# Telex-O.net
KiCad netlist of a schematic drawn in EAGLE
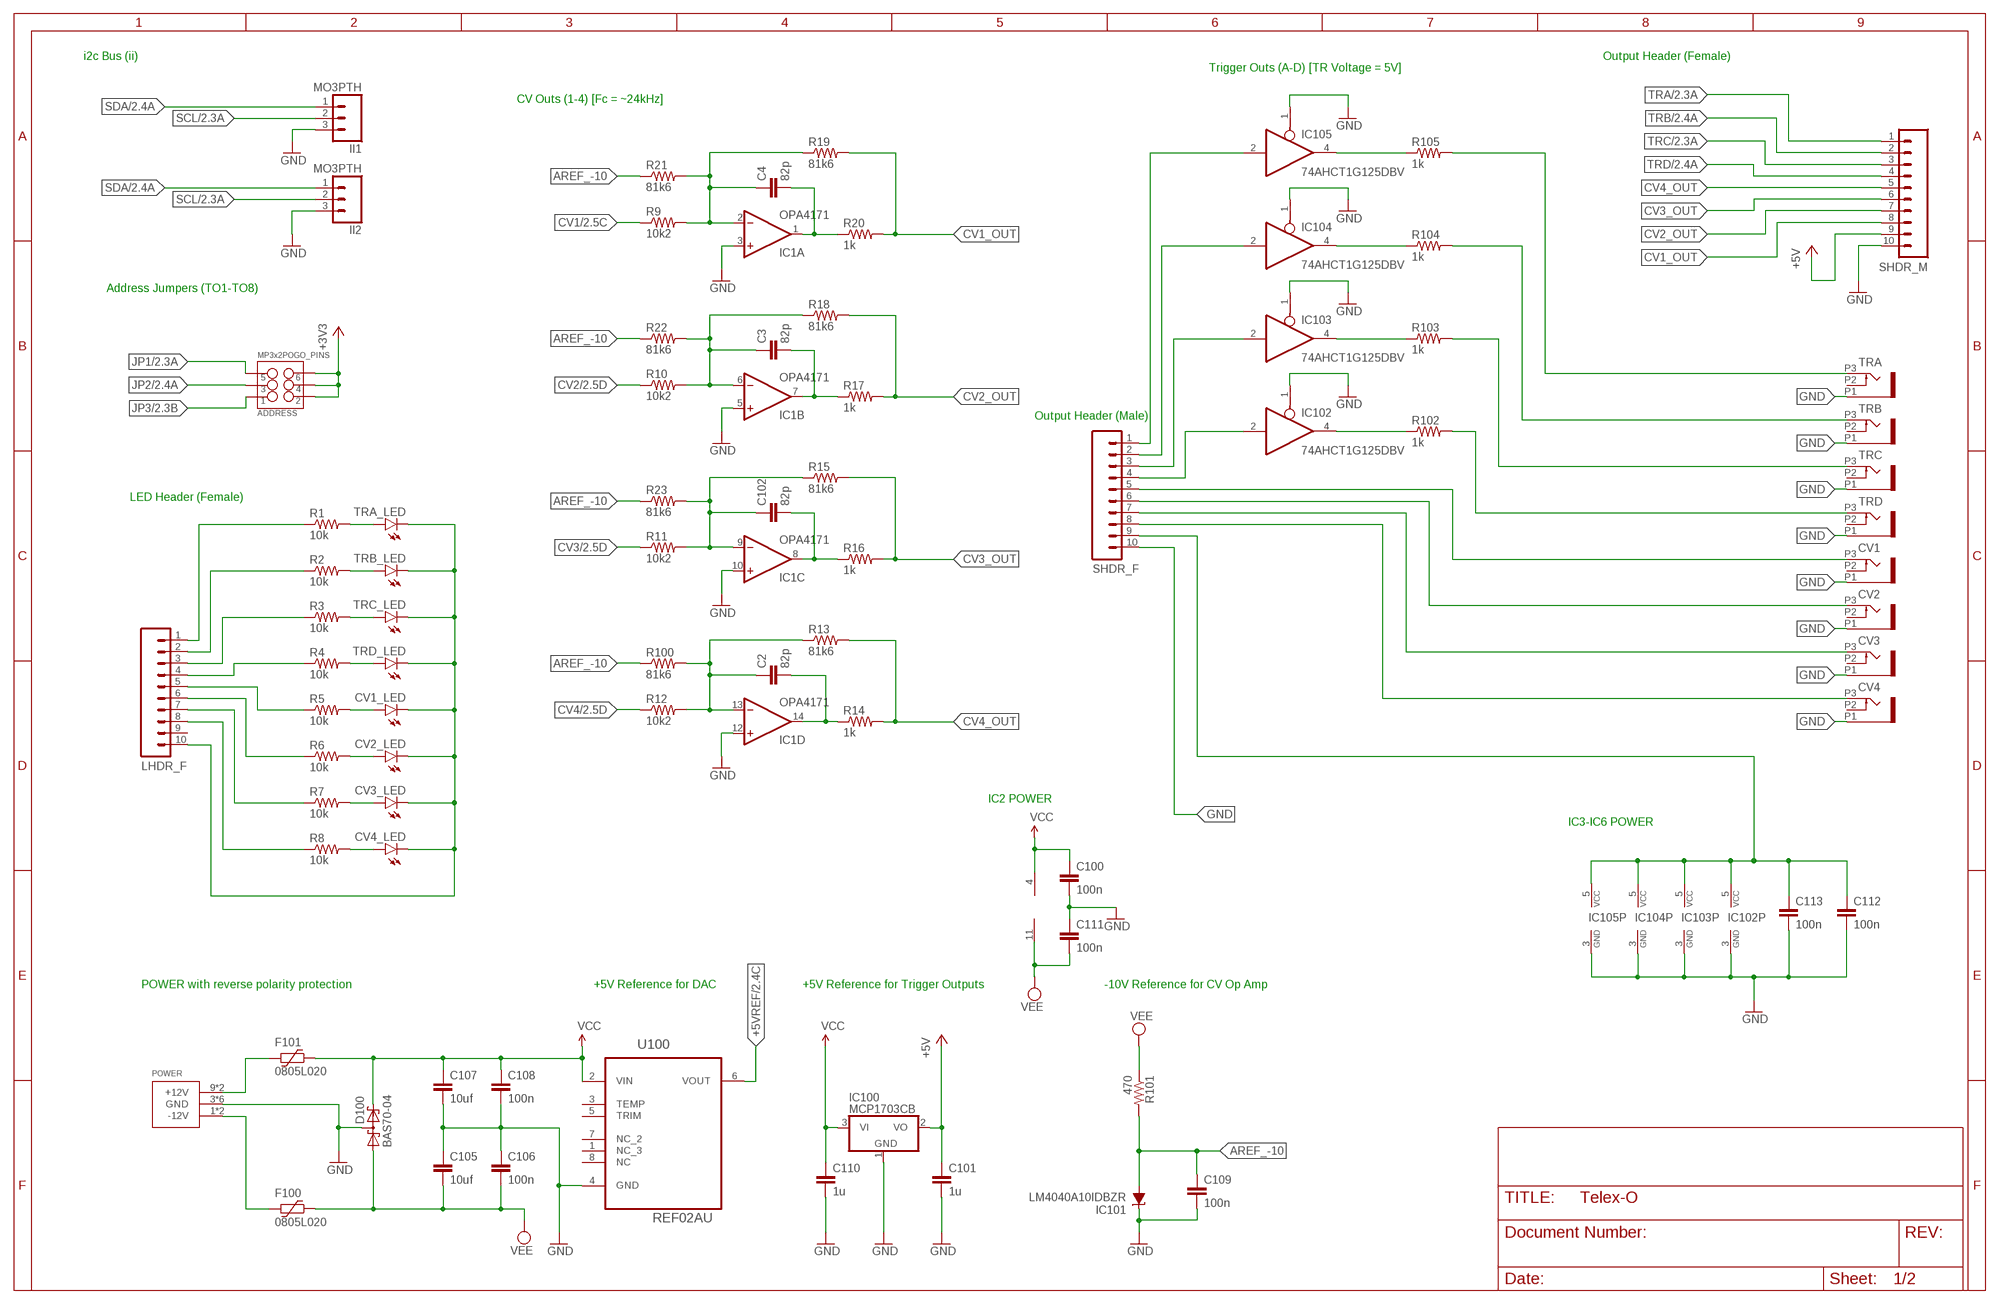
[diagram p0: schematic, sheet 1]
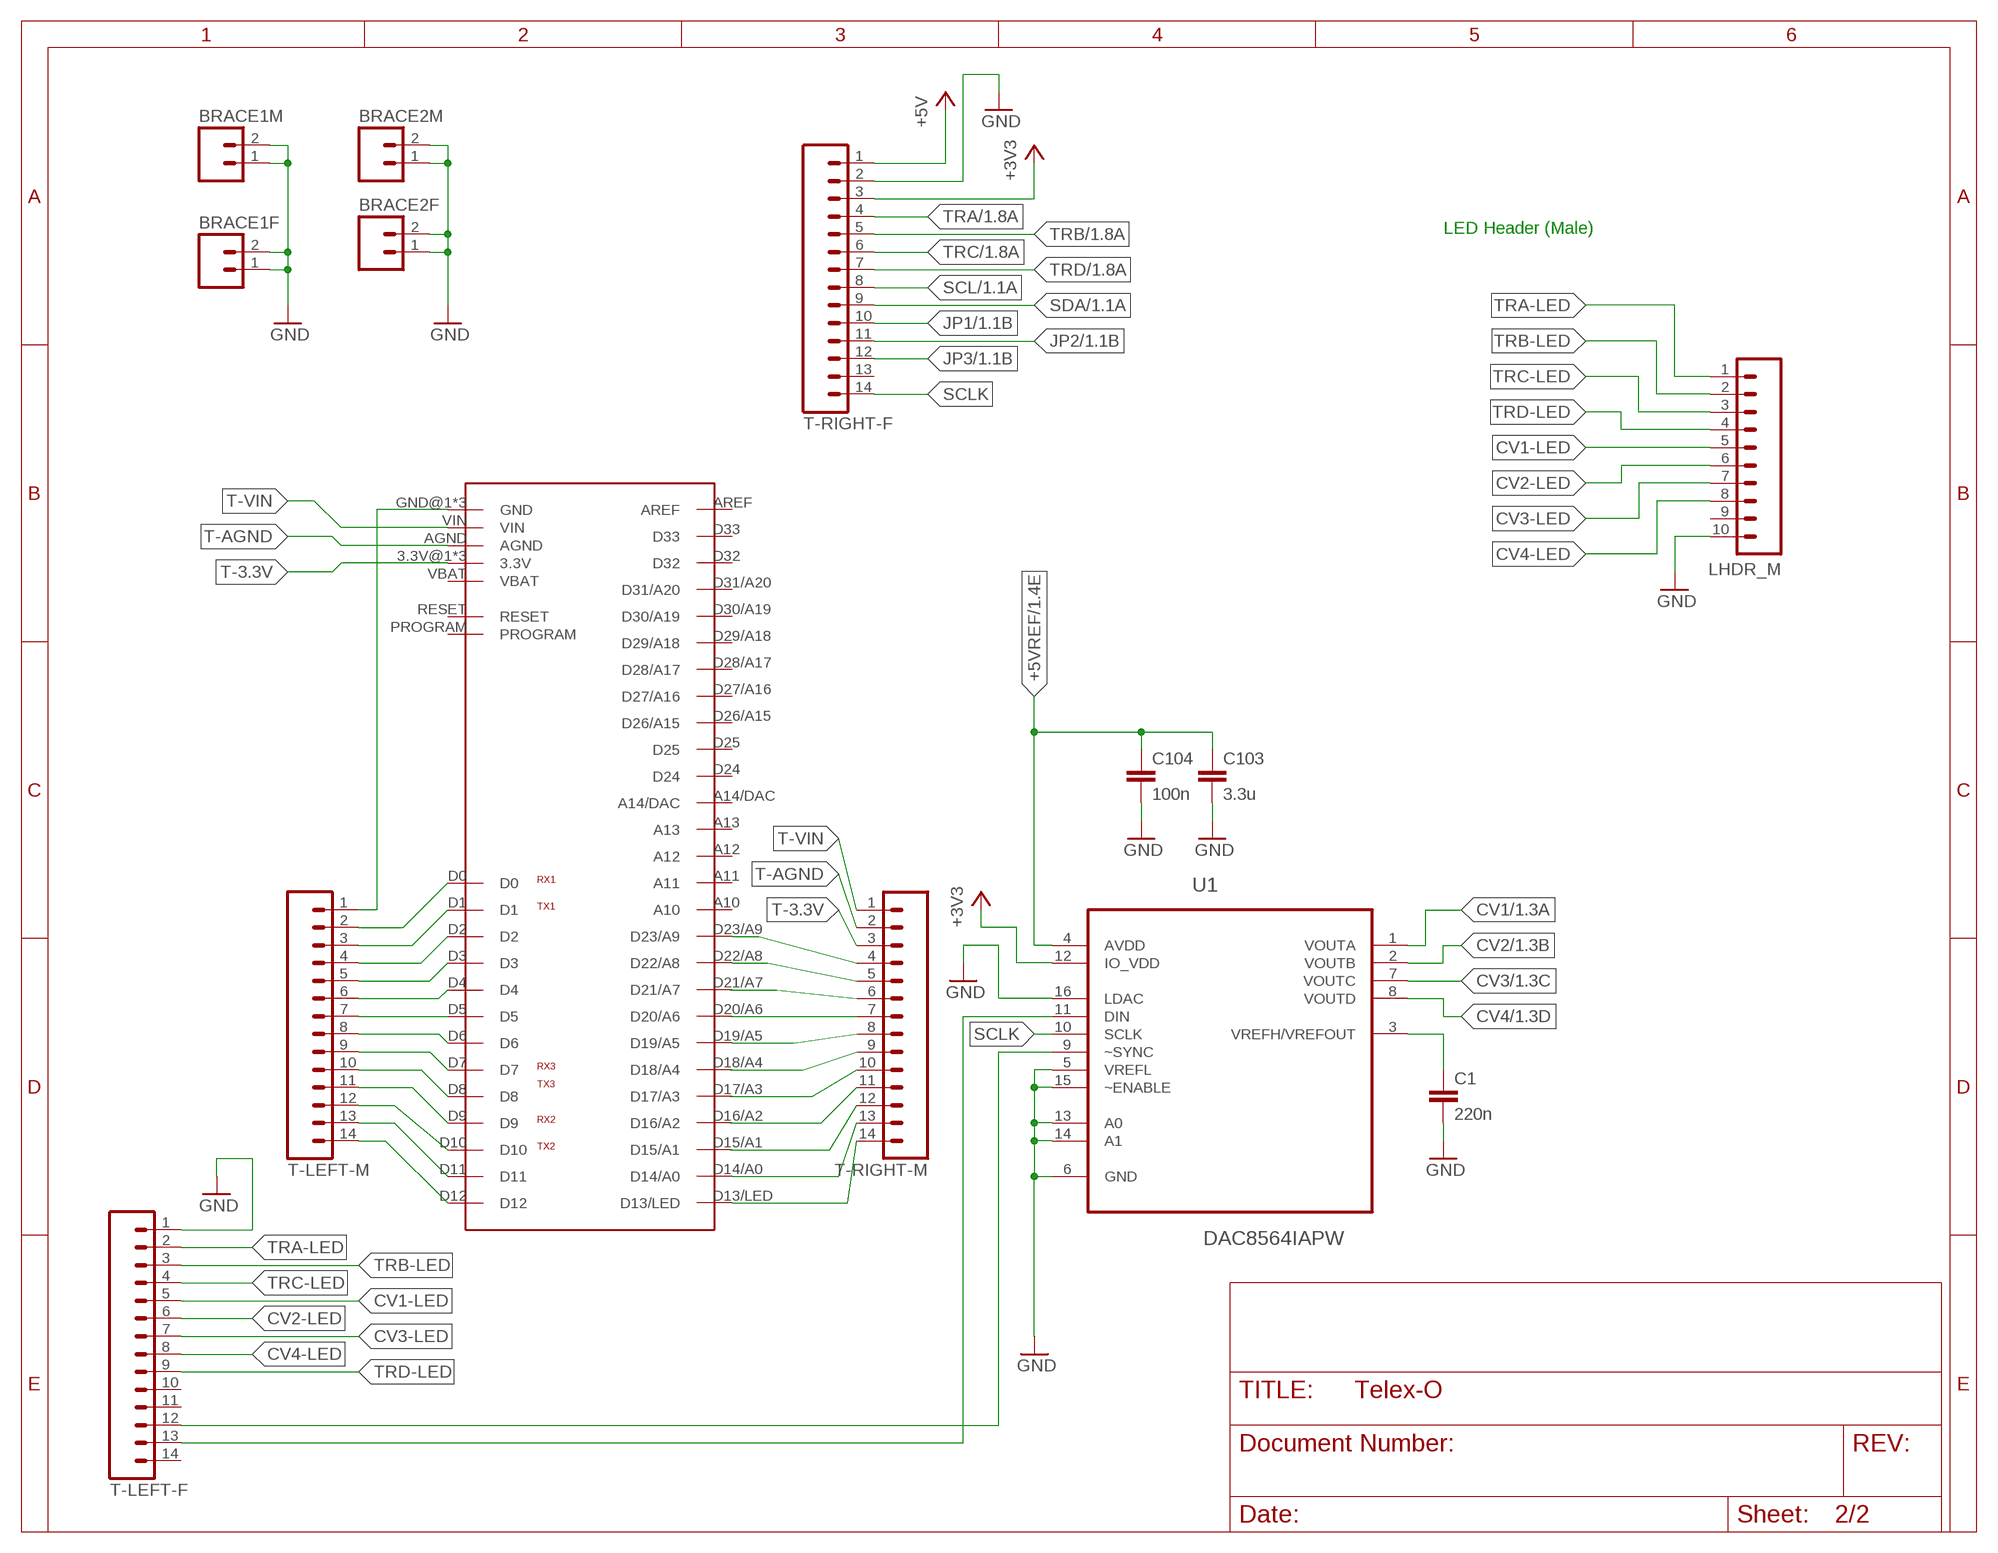
[diagram p1: schematic, sheet 2]

(export (version "E")
  (design (tool "Eeschema 10.0.6"))
  (components
    (comp (ref "BRACE1F")
      (value "M02PTH")
      (footprint "eagle-import:1X02")
      (libsource (lib "eagle-import") (part "M02PTH"))
    )
    (comp (ref "BRACE1M")
      (value "M02PTH")
      (footprint "eagle-import:1X02")
      (libsource (lib "eagle-import") (part "M02PTH"))
    )
    (comp (ref "BRACE2F")
      (value "M02PTH")
      (footprint "eagle-import:1X02")
      (libsource (lib "eagle-import") (part "M02PTH"))
    )
    (comp (ref "BRACE2M")
      (value "M02PTH")
      (footprint "eagle-import:1X02")
      (libsource (lib "eagle-import") (part "M02PTH"))
    )
    (comp (ref "C1")
      (value "220n")
      (footprint "eagle-import:0603-CAP")
      (libsource (lib "eagle-import") (part "CAP0603-CAP"))
    )
    (comp (ref "C103")
      (value "3.3u")
      (footprint "eagle-import:1206")
      (libsource (lib "eagle-import") (part "CAP1206"))
    )
    (comp (ref "C104")
      (value "100n")
      (footprint "eagle-import:0603-CAP")
      (libsource (lib "eagle-import") (part "CAP0603-CAP"))
    )
    (comp (ref "LHDR_M")
      (value "M10SILK_FEMALE_PTH")
      (footprint "eagle-import:1X10")
      (libsource (lib "eagle-import") (part "M10SILK_FEMALE_PTH"))
    )
    (comp (ref "T-LEFT-F")
      (value "M14")
      (footprint "eagle-import:1X14")
      (libsource (lib "eagle-import") (part "M14"))
    )
    (comp (ref "T-LEFT-M")
      (value "M14")
      (footprint "eagle-import:1X14")
      (libsource (lib "eagle-import") (part "M14"))
    )
    (comp (ref "T-RIGHT-F")
      (value "M14")
      (footprint "eagle-import:1X14")
      (libsource (lib "eagle-import") (part "M14"))
    )
    (comp (ref "T-RIGHT-M")
      (value "M14")
      (footprint "eagle-import:1X14")
      (libsource (lib "eagle-import") (part "M14"))
    )
    (comp (ref "U$1")
      (value "TEENSY3.1_ALL")
      (footprint "eagle-import:TEENSY3.1_ALL")
      (libsource (lib "eagle-import") (part "TEENSY3.1_ALL"))
    )
    (comp (ref "U1")
      (value "DAC8564IAPW")
      (footprint "eagle-import:SOP65P640X120-16N")
      (libsource (lib "eagle-import") (part "DAC8564IAPW"))
    )
    (comp (ref "ADDRESS")
      (value "MP3x2POGO_PINS")
      (footprint "eagle-import:2X3_POGO")
      (libsource (lib "eagle-import") (part "M03X2POGO_PINS"))
    )
    (comp (ref "C2")
      (value "82p")
      (footprint "eagle-import:1206")
      (libsource (lib "eagle-import") (part "CAP1206"))
    )
    (comp (ref "C3")
      (value "82p")
      (footprint "eagle-import:1206")
      (libsource (lib "eagle-import") (part "CAP1206"))
    )
    (comp (ref "C4")
      (value "82p")
      (footprint "eagle-import:1206")
      (libsource (lib "eagle-import") (part "CAP1206"))
    )
    (comp (ref "C100")
      (value "100n")
      (footprint "eagle-import:0603-CAP")
      (libsource (lib "eagle-import") (part "CAP0603-CAP"))
    )
    (comp (ref "C101")
      (value "1u")
      (footprint "eagle-import:0603-CAP")
      (libsource (lib "eagle-import") (part "CAP0603-CAP"))
    )
    (comp (ref "C102")
      (value "82p")
      (footprint "eagle-import:1206")
      (libsource (lib "eagle-import") (part "CAP1206"))
    )
    (comp (ref "C105")
      (value "10uf")
      (footprint "eagle-import:1206")
      (libsource (lib "eagle-import") (part "CAP1206"))
    )
    (comp (ref "C106")
      (value "100n")
      (footprint "eagle-import:0603-CAP")
      (libsource (lib "eagle-import") (part "CAP0603-CAP"))
    )
    (comp (ref "C107")
      (value "10uf")
      (footprint "eagle-import:1206")
      (libsource (lib "eagle-import") (part "CAP1206"))
    )
    (comp (ref "C108")
      (value "100n")
      (footprint "eagle-import:0603-CAP")
      (libsource (lib "eagle-import") (part "CAP0603-CAP"))
    )
    (comp (ref "C109")
      (value "100n")
      (footprint "eagle-import:0603-CAP")
      (libsource (lib "eagle-import") (part "CAP0603-CAP"))
    )
    (comp (ref "C110")
      (value "1u")
      (footprint "eagle-import:0603-CAP")
      (libsource (lib "eagle-import") (part "CAP0603-CAP"))
    )
    (comp (ref "C111")
      (value "100n")
      (footprint "eagle-import:0603-CAP")
      (libsource (lib "eagle-import") (part "CAP0603-CAP"))
    )
    (comp (ref "C112")
      (value "100n")
      (footprint "eagle-import:0603-CAP")
      (libsource (lib "eagle-import") (part "CAP0603-CAP"))
    )
    (comp (ref "C113")
      (value "100n")
      (footprint "eagle-import:0603-CAP")
      (libsource (lib "eagle-import") (part "CAP0603-CAP"))
    )
    (comp (ref "CV1")
      (value "EURO_JACKS-7")
      (footprint "eagle-import:WQP_PJ_301M")
      (libsource (lib "eagle-import") (part "EURO_JACKS-7"))
    )
    (comp (ref "CV1_LED")
      (value "LED3MM")
      (footprint "eagle-import:LED3MM")
      (libsource (lib "eagle-import") (part "LED3MM"))
    )
    (comp (ref "CV2")
      (value "EURO_JACKS-7")
      (footprint "eagle-import:WQP_PJ_301M")
      (libsource (lib "eagle-import") (part "EURO_JACKS-7"))
    )
    (comp (ref "CV2_LED")
      (value "LED3MM")
      (footprint "eagle-import:LED3MM")
      (libsource (lib "eagle-import") (part "LED3MM"))
    )
    (comp (ref "CV3")
      (value "EURO_JACKS-7")
      (footprint "eagle-import:WQP_PJ_301M")
      (libsource (lib "eagle-import") (part "EURO_JACKS-7"))
    )
    (comp (ref "CV3_LED")
      (value "LED3MM")
      (footprint "eagle-import:LED3MM")
      (libsource (lib "eagle-import") (part "LED3MM"))
    )
    (comp (ref "CV4")
      (value "EURO_JACKS-7")
      (footprint "eagle-import:WQP_PJ_301M")
      (libsource (lib "eagle-import") (part "EURO_JACKS-7"))
    )
    (comp (ref "CV4_LED")
      (value "LED3MM")
      (footprint "eagle-import:LED3MM")
      (libsource (lib "eagle-import") (part "LED3MM"))
    )
    (comp (ref "D100")
      (value "BAS70-04")
      (footprint "eagle-import:SOT23")
      (libsource (lib "eagle-import") (part "BAS70-04"))
    )
    (comp (ref "F100")
      (value "0805L020")
      (footprint "eagle-import:0805L")
      (fields (field (name "MF") "Littelfuse"))
      (libsource (lib "eagle-import") (part "?0805L020"))
    )
    (comp (ref "F101")
      (value "0805L020")
      (footprint "eagle-import:0805L")
      (fields (field (name "MF") "Littelfuse"))
      (libsource (lib "eagle-import") (part "?0805L020"))
    )
    (comp (ref "IC1")
      (value "OPA4171")
      (footprint "eagle-import:SO14")
      (libsource (lib "eagle-import") (part "TL074D"))
    )
    (comp (ref "IC100")
      (value "MCP1703CB")
      (footprint "eagle-import:SOT23")
      (libsource (lib "eagle-import") (part "MCP1703CB"))
    )
    (comp (ref "IC101")
      (value "LM4040A10IDBZR")
      (footprint "eagle-import:DBZ_R-PDSO-G3")
      (fields (field (name "MPN") "LM4041A12IDBZR"))
      (libsource (lib "eagle-import") (part "LM4041DBZA12"))
    )
    (comp (ref "IC102")
      (value "74AHCT1G125DBV")
      (footprint "eagle-import:SOT23-5")
      (libsource (lib "eagle-import") (part "741G125DBVAHCT"))
    )
    (comp (ref "IC103")
      (value "74AHCT1G125DBV")
      (footprint "eagle-import:SOT23-5")
      (libsource (lib "eagle-import") (part "741G125DBVAHCT"))
    )
    (comp (ref "IC104")
      (value "74AHCT1G125DBV")
      (footprint "eagle-import:SOT23-5")
      (libsource (lib "eagle-import") (part "741G125DBVAHCT"))
    )
    (comp (ref "IC105")
      (value "74AHCT1G125DBV")
      (footprint "eagle-import:SOT23-5")
      (libsource (lib "eagle-import") (part "741G125DBVAHCT"))
    )
    (comp (ref "II1")
      (value "MO3PTH")
      (footprint "eagle-import:1X03")
      (libsource (lib "eagle-import") (part "M03PTH"))
    )
    (comp (ref "II2")
      (value "MO3PTH")
      (footprint "eagle-import:1X03")
      (libsource (lib "eagle-import") (part "M03PTH"))
    )
    (comp (ref "LHDR_F")
      (value "M10SILK_FEMALE_PTH")
      (footprint "eagle-import:1X10")
      (libsource (lib "eagle-import") (part "M10SILK_FEMALE_PTH"))
    )
    (comp (ref "POWER")
      (value "10-Pin")
      (footprint "eagle-import:POWER_10")
      (libsource (lib "eagle-import") (part "POWER_SIMPLE10"))
    )
    (comp (ref "R1")
      (value "10k")
      (footprint "eagle-import:R0603")
      (libsource (lib "eagle-import") (part "R-US_R0603"))
    )
    (comp (ref "R2")
      (value "10k")
      (footprint "eagle-import:R0603")
      (libsource (lib "eagle-import") (part "R-US_R0603"))
    )
    (comp (ref "R3")
      (value "10k")
      (footprint "eagle-import:R0603")
      (libsource (lib "eagle-import") (part "R-US_R0603"))
    )
    (comp (ref "R4")
      (value "10k")
      (footprint "eagle-import:R0603")
      (libsource (lib "eagle-import") (part "R-US_R0603"))
    )
    (comp (ref "R5")
      (value "10k")
      (footprint "eagle-import:R0603")
      (libsource (lib "eagle-import") (part "R-US_R0603"))
    )
    (comp (ref "R6")
      (value "10k")
      (footprint "eagle-import:R0603")
      (libsource (lib "eagle-import") (part "R-US_R0603"))
    )
    (comp (ref "R7")
      (value "10k")
      (footprint "eagle-import:R0603")
      (libsource (lib "eagle-import") (part "R-US_R0603"))
    )
    (comp (ref "R8")
      (value "10k")
      (footprint "eagle-import:R0603")
      (libsource (lib "eagle-import") (part "R-US_R0603"))
    )
    (comp (ref "R9")
      (value "10k2")
      (footprint "eagle-import:R0603")
      (libsource (lib "eagle-import") (part "R-US_R0603"))
    )
    (comp (ref "R10")
      (value "10k2")
      (footprint "eagle-import:R0603")
      (libsource (lib "eagle-import") (part "R-US_R0603"))
    )
    (comp (ref "R11")
      (value "10k2")
      (footprint "eagle-import:R0603")
      (libsource (lib "eagle-import") (part "R-US_R0603"))
    )
    (comp (ref "R12")
      (value "10k2")
      (footprint "eagle-import:R0603")
      (libsource (lib "eagle-import") (part "R-US_R0603"))
    )
    (comp (ref "R13")
      (value "81k6")
      (footprint "eagle-import:R0603")
      (libsource (lib "eagle-import") (part "R-US_R0603"))
    )
    (comp (ref "R14")
      (value "1k")
      (footprint "eagle-import:R0603")
      (libsource (lib "eagle-import") (part "R-US_R0603"))
    )
    (comp (ref "R15")
      (value "81k6")
      (footprint "eagle-import:R0603")
      (libsource (lib "eagle-import") (part "R-US_R0603"))
    )
    (comp (ref "R16")
      (value "1k")
      (footprint "eagle-import:R0603")
      (libsource (lib "eagle-import") (part "R-US_R0603"))
    )
    (comp (ref "R17")
      (value "1k")
      (footprint "eagle-import:R0603")
      (libsource (lib "eagle-import") (part "R-US_R0603"))
    )
    (comp (ref "R18")
      (value "81k6")
      (footprint "eagle-import:R0603")
      (libsource (lib "eagle-import") (part "R-US_R0603"))
    )
    (comp (ref "R19")
      (value "81k6")
      (footprint "eagle-import:R0603")
      (libsource (lib "eagle-import") (part "R-US_R0603"))
    )
    (comp (ref "R20")
      (value "1k")
      (footprint "eagle-import:R0603")
      (libsource (lib "eagle-import") (part "R-US_R0603"))
    )
    (comp (ref "R21")
      (value "81k6")
      (footprint "eagle-import:R0603")
      (libsource (lib "eagle-import") (part "R-US_R0603"))
    )
    (comp (ref "R22")
      (value "81k6")
      (footprint "eagle-import:R0603")
      (libsource (lib "eagle-import") (part "R-US_R0603"))
    )
    (comp (ref "R23")
      (value "81k6")
      (footprint "eagle-import:R0603")
      (libsource (lib "eagle-import") (part "R-US_R0603"))
    )
    (comp (ref "R100")
      (value "81k6")
      (footprint "eagle-import:R0603")
      (libsource (lib "eagle-import") (part "R-US_R0603"))
    )
    (comp (ref "R101")
      (value "470")
      (footprint "eagle-import:R0603")
      (libsource (lib "eagle-import") (part "R-US_R0603"))
    )
    (comp (ref "R102")
      (value "1k")
      (footprint "eagle-import:R0603")
      (libsource (lib "eagle-import") (part "R-US_R0603"))
    )
    (comp (ref "R103")
      (value "1k")
      (footprint "eagle-import:R0603")
      (libsource (lib "eagle-import") (part "R-US_R0603"))
    )
    (comp (ref "R104")
      (value "1k")
      (footprint "eagle-import:R0603")
      (libsource (lib "eagle-import") (part "R-US_R0603"))
    )
    (comp (ref "R105")
      (value "1k")
      (footprint "eagle-import:R0603")
      (libsource (lib "eagle-import") (part "R-US_R0603"))
    )
    (comp (ref "SHDR_F")
      (value "M10SILK_FEMALE_PTH")
      (footprint "eagle-import:1X10")
      (libsource (lib "eagle-import") (part "M10SILK_FEMALE_PTH"))
    )
    (comp (ref "SHDR_M")
      (value "M10SILK_FEMALE_PTH")
      (footprint "eagle-import:1X10")
      (libsource (lib "eagle-import") (part "M10SILK_FEMALE_PTH"))
    )
    (comp (ref "TRA")
      (value "EURO_JACKS-7")
      (footprint "eagle-import:WQP_PJ_301M")
      (libsource (lib "eagle-import") (part "EURO_JACKS-7"))
    )
    (comp (ref "TRA_LED")
      (value "LED3MM")
      (footprint "eagle-import:LED3MM")
      (libsource (lib "eagle-import") (part "LED3MM"))
    )
    (comp (ref "TRB")
      (value "EURO_JACKS-7")
      (footprint "eagle-import:WQP_PJ_301M")
      (libsource (lib "eagle-import") (part "EURO_JACKS-7"))
    )
    (comp (ref "TRB_LED")
      (value "LED3MM")
      (footprint "eagle-import:LED3MM")
      (libsource (lib "eagle-import") (part "LED3MM"))
    )
    (comp (ref "TRC")
      (value "EURO_JACKS-7")
      (footprint "eagle-import:WQP_PJ_301M")
      (libsource (lib "eagle-import") (part "EURO_JACKS-7"))
    )
    (comp (ref "TRC_LED")
      (value "LED3MM")
      (footprint "eagle-import:LED3MM")
      (libsource (lib "eagle-import") (part "LED3MM"))
    )
    (comp (ref "TRD")
      (value "EURO_JACKS-7")
      (footprint "eagle-import:WQP_PJ_301M")
      (libsource (lib "eagle-import") (part "EURO_JACKS-7"))
    )
    (comp (ref "TRD_LED")
      (value "LED3MM")
      (footprint "eagle-import:LED3MM")
      (libsource (lib "eagle-import") (part "LED3MM"))
    )
    (comp (ref "U100")
      (value "REF02AU")
      (footprint "eagle-import:SOIC127P600X175-8N")
      (libsource (lib "eagle-import") (part "REF02AU"))
    )
  )
  (nets
    (net (code "1") (name "+3V3") (class "Default")
      (node (ref "ADDRESS") (pin "P$2") (pinfunction "2_P$2") (pintype "bidirectional"))
      (node (ref "ADDRESS") (pin "P$4") (pinfunction "4_P$4") (pintype "bidirectional"))
      (node (ref "ADDRESS") (pin "P$6") (pinfunction "6_P$6") (pintype "bidirectional"))
      (node (ref "T-RIGHT-F") (pin "3") (pinfunction "3_3") (pintype "passive"))
      (node (ref "U1") (pin "12") (pinfunction "IO_VDD_12") (pintype "power_in"))
    )
    (net (code "2") (name "+5V") (class "Default")
      (node (ref "C101") (pin "1") (pinfunction "1_1") (pintype "passive"))
      (node (ref "IC100") (pin "2") (pinfunction "VO_2") (pintype "passive"))
      (node (ref "SHDR_M") (pin "9") (pinfunction "9_9") (pintype "passive"))
      (node (ref "T-RIGHT-F") (pin "1") (pinfunction "1_1") (pintype "passive"))
    )
    (net (code "3") (name "+5VREF") (class "Default")
      (node (ref "C103") (pin "1") (pinfunction "1_1") (pintype "passive"))
      (node (ref "C104") (pin "1") (pinfunction "1_1") (pintype "passive"))
      (node (ref "U1") (pin "4") (pinfunction "AVDD_4") (pintype "power_in"))
      (node (ref "U100") (pin "6") (pinfunction "VOUT_6") (pintype "output"))
    )
    (net (code "4") (name "AREF_-10") (class "Default")
      (node (ref "C109") (pin "1") (pinfunction "1_1") (pintype "passive"))
      (node (ref "IC101") (pin "2") (pinfunction "A_2") (pintype "passive"))
      (node (ref "R100") (pin "1") (pinfunction "1_1") (pintype "passive"))
      (node (ref "R101") (pin "2") (pinfunction "2_2") (pintype "passive"))
      (node (ref "R21") (pin "1") (pinfunction "1_1") (pintype "passive"))
      (node (ref "R22") (pin "1") (pinfunction "1_1") (pintype "passive"))
      (node (ref "R23") (pin "1") (pinfunction "1_1") (pintype "passive"))
    )
    (net (code "5") (name "CV1") (class "Default")
      (node (ref "R9") (pin "1") (pinfunction "1_1") (pintype "passive"))
      (node (ref "U1") (pin "1") (pinfunction "VOUTA_1") (pintype "output"))
    )
    (net (code "6") (name "CV1-LED") (class "Default")
      (node (ref "LHDR_M") (pin "5") (pinfunction "5_5") (pintype "passive"))
      (node (ref "T-LEFT-F") (pin "5") (pinfunction "5_5") (pintype "passive"))
    )
    (net (code "7") (name "CV1_OUT") (class "Default")
      (node (ref "R19") (pin "2") (pinfunction "2_2") (pintype "passive"))
      (node (ref "R20") (pin "2") (pinfunction "2_2") (pintype "passive"))
      (node (ref "SHDR_M") (pin "8") (pinfunction "8_8") (pintype "passive"))
    )
    (net (code "8") (name "CV2") (class "Default")
      (node (ref "R10") (pin "1") (pinfunction "1_1") (pintype "passive"))
      (node (ref "U1") (pin "2") (pinfunction "VOUTB_2") (pintype "output"))
    )
    (net (code "9") (name "CV2-LED") (class "Default")
      (node (ref "LHDR_M") (pin "6") (pinfunction "6_6") (pintype "passive"))
      (node (ref "T-LEFT-F") (pin "6") (pinfunction "6_6") (pintype "passive"))
    )
    (net (code "10") (name "CV2_OUT") (class "Default")
      (node (ref "R17") (pin "2") (pinfunction "2_2") (pintype "passive"))
      (node (ref "R18") (pin "2") (pinfunction "2_2") (pintype "passive"))
      (node (ref "SHDR_M") (pin "7") (pinfunction "7_7") (pintype "passive"))
    )
    (net (code "11") (name "CV3") (class "Default")
      (node (ref "R11") (pin "1") (pinfunction "1_1") (pintype "passive"))
      (node (ref "U1") (pin "7") (pinfunction "VOUTC_7") (pintype "output"))
    )
    (net (code "12") (name "CV3-LED") (class "Default")
      (node (ref "LHDR_M") (pin "7") (pinfunction "7_7") (pintype "passive"))
      (node (ref "T-LEFT-F") (pin "7") (pinfunction "7_7") (pintype "passive"))
    )
    (net (code "13") (name "CV3_OUT") (class "Default")
      (node (ref "R15") (pin "2") (pinfunction "2_2") (pintype "passive"))
      (node (ref "R16") (pin "2") (pinfunction "2_2") (pintype "passive"))
      (node (ref "SHDR_M") (pin "6") (pinfunction "6_6") (pintype "passive"))
    )
    (net (code "14") (name "CV4") (class "Default")
      (node (ref "R12") (pin "1") (pinfunction "1_1") (pintype "passive"))
      (node (ref "U1") (pin "8") (pinfunction "VOUTD_8") (pintype "output"))
    )
    (net (code "15") (name "CV4-LED") (class "Default")
      (node (ref "LHDR_M") (pin "8") (pinfunction "8_8") (pintype "passive"))
      (node (ref "T-LEFT-F") (pin "8") (pinfunction "8_8") (pintype "passive"))
    )
    (net (code "16") (name "CV4_OUT") (class "Default")
      (node (ref "R13") (pin "2") (pinfunction "2_2") (pintype "passive"))
      (node (ref "R14") (pin "2") (pinfunction "2_2") (pintype "passive"))
      (node (ref "SHDR_M") (pin "5") (pinfunction "5_5") (pintype "passive"))
    )
    (net (code "17") (name "GND") (class "Default")
      (node (ref "BRACE1F") (pin "1") (pinfunction "1_1") (pintype "passive"))
      (node (ref "BRACE1F") (pin "2") (pinfunction "2_2") (pintype "passive"))
      (node (ref "BRACE1M") (pin "1") (pinfunction "1_1") (pintype "passive"))
      (node (ref "BRACE1M") (pin "2") (pinfunction "2_2") (pintype "passive"))
      (node (ref "BRACE2F") (pin "1") (pinfunction "1_1") (pintype "passive"))
      (node (ref "BRACE2F") (pin "2") (pinfunction "2_2") (pintype "passive"))
      (node (ref "BRACE2M") (pin "1") (pinfunction "1_1") (pintype "passive"))
      (node (ref "BRACE2M") (pin "2") (pinfunction "2_2") (pintype "passive"))
      (node (ref "C1") (pin "2") (pinfunction "2_2") (pintype "passive"))
      (node (ref "C100") (pin "2") (pinfunction "2_2") (pintype "passive"))
      (node (ref "C101") (pin "2") (pinfunction "2_2") (pintype "passive"))
      (node (ref "C103") (pin "2") (pinfunction "2_2") (pintype "passive"))
      (node (ref "C104") (pin "2") (pinfunction "2_2") (pintype "passive"))
      (node (ref "C105") (pin "1") (pinfunction "1_1") (pintype "passive"))
      (node (ref "C106") (pin "1") (pinfunction "1_1") (pintype "passive"))
      (node (ref "C107") (pin "2") (pinfunction "2_2") (pintype "passive"))
      (node (ref "C108") (pin "2") (pinfunction "2_2") (pintype "passive"))
      (node (ref "C109") (pin "2") (pinfunction "2_2") (pintype "passive"))
      (node (ref "C110") (pin "2") (pinfunction "2_2") (pintype "passive"))
      (node (ref "C111") (pin "1") (pinfunction "1_1") (pintype "passive"))
      (node (ref "C112") (pin "2") (pinfunction "2_2") (pintype "passive"))
      (node (ref "C113") (pin "2") (pinfunction "2_2") (pintype "passive"))
      (node (ref "CV1") (pin "P1") (pinfunction "1_P1") (pintype "passive"))
      (node (ref "CV1_LED") (pin "K") (pinfunction "C_K") (pintype "passive"))
      (node (ref "CV2") (pin "P1") (pinfunction "1_P1") (pintype "passive"))
      (node (ref "CV2_LED") (pin "K") (pinfunction "C_K") (pintype "passive"))
      (node (ref "CV3") (pin "P1") (pinfunction "1_P1") (pintype "passive"))
      (node (ref "CV3_LED") (pin "K") (pinfunction "C_K") (pintype "passive"))
      (node (ref "CV4") (pin "P1") (pinfunction "1_P1") (pintype "passive"))
      (node (ref "CV4_LED") (pin "K") (pinfunction "C_K") (pintype "passive"))
      (node (ref "D100") (pin "3") (pinfunction "C1A2_3") (pintype "passive"))
      (node (ref "IC1") (pin "10") (pinfunction "+IN_10") (pintype "input"))
      (node (ref "IC1") (pin "12") (pinfunction "+IN_12") (pintype "input"))
      (node (ref "IC1") (pin "3") (pinfunction "+IN_3") (pintype "input"))
      (node (ref "IC1") (pin "5") (pinfunction "+IN_5") (pintype "input"))
      (node (ref "IC100") (pin "1") (pinfunction "GND_1") (pintype "passive"))
      (node (ref "IC101") (pin "1") (pinfunction "C_1") (pintype "passive"))
      (node (ref "IC102") (pin "1") (pinfunction "OE_1") (pintype "input"))
      (node (ref "IC102") (pin "3") (pinfunction "GND_3") (pintype "power_in"))
      (node (ref "IC103") (pin "1") (pinfunction "OE_1") (pintype "input"))
      (node (ref "IC103") (pin "3") (pinfunction "GND_3") (pintype "power_in"))
      (node (ref "IC104") (pin "1") (pinfunction "OE_1") (pintype "input"))
      (node (ref "IC104") (pin "3") (pinfunction "GND_3") (pintype "power_in"))
      (node (ref "IC105") (pin "1") (pinfunction "OE_1") (pintype "input"))
      (node (ref "IC105") (pin "3") (pinfunction "GND_3") (pintype "power_in"))
      (node (ref "II1") (pin "3") (pinfunction "3_3") (pintype "passive"))
      (node (ref "II2") (pin "3") (pinfunction "3_3") (pintype "passive"))
      (node (ref "LHDR_F") (pin "10") (pinfunction "10_10") (pintype "passive"))
      (node (ref "LHDR_M") (pin "10") (pinfunction "10_10") (pintype "passive"))
      (node (ref "POWER") (pin "3") (pinfunction "GND_3") (pintype "bidirectional"))
      (node (ref "POWER") (pin "4") (pinfunction "GND_4") (pintype "bidirectional"))
      (node (ref "POWER") (pin "5") (pinfunction "GND_5") (pintype "bidirectional"))
      (node (ref "POWER") (pin "6") (pinfunction "GND_6") (pintype "bidirectional"))
      (node (ref "POWER") (pin "7") (pinfunction "GND_7") (pintype "bidirectional"))
      (node (ref "POWER") (pin "8") (pinfunction "GND_8") (pintype "bidirectional"))
      (node (ref "SHDR_F") (pin "10") (pinfunction "10_10") (pintype "passive"))
      (node (ref "SHDR_M") (pin "10") (pinfunction "10_10") (pintype "passive"))
      (node (ref "T-LEFT-F") (pin "1") (pinfunction "1_1") (pintype "passive"))
      (node (ref "T-RIGHT-F") (pin "2") (pinfunction "2_2") (pintype "passive"))
      (node (ref "TRA") (pin "P1") (pinfunction "1_P1") (pintype "passive"))
      (node (ref "TRA_LED") (pin "K") (pinfunction "C_K") (pintype "passive"))
      (node (ref "TRB") (pin "P1") (pinfunction "1_P1") (pintype "passive"))
      (node (ref "TRB_LED") (pin "K") (pinfunction "C_K") (pintype "passive"))
      (node (ref "TRC") (pin "P1") (pinfunction "1_P1") (pintype "passive"))
      (node (ref "TRC_LED") (pin "K") (pinfunction "C_K") (pintype "passive"))
      (node (ref "TRD") (pin "P1") (pinfunction "1_P1") (pintype "passive"))
      (node (ref "TRD_LED") (pin "K") (pinfunction "C_K") (pintype "passive"))
      (node (ref "U1") (pin "13") (pinfunction "A0_13") (pintype "input"))
      (node (ref "U1") (pin "14") (pinfunction "A1_14") (pintype "input"))
      (node (ref "U1") (pin "15") (pinfunction "~{ENABLE}_15") (pintype "input"))
      (node (ref "U1") (pin "16") (pinfunction "LDAC_16") (pintype "input"))
      (node (ref "U1") (pin "5") (pinfunction "VREFL_5") (pintype "input"))
      (node (ref "U1") (pin "6") (pinfunction "GND_6") (pintype "passive"))
      (node (ref "U100") (pin "4") (pinfunction "GND_4") (pintype "passive"))
    )
    (net (code "18") (name "JP1") (class "Default")
      (node (ref "ADDRESS") (pin "P$5") (pinfunction "5_P$5") (pintype "bidirectional"))
      (node (ref "T-RIGHT-F") (pin "10") (pinfunction "10_10") (pintype "passive"))
    )
    (net (code "19") (name "JP2") (class "Default")
      (node (ref "ADDRESS") (pin "P$3") (pinfunction "3_P$3") (pintype "bidirectional"))
      (node (ref "T-RIGHT-F") (pin "11") (pinfunction "11_11") (pintype "passive"))
    )
    (net (code "20") (name "JP3") (class "Default")
      (node (ref "ADDRESS") (pin "P$1") (pinfunction "1_P$1") (pintype "bidirectional"))
      (node (ref "T-RIGHT-F") (pin "12") (pinfunction "12_12") (pintype "passive"))
    )
    (net (code "21") (name "Net-(CV1-3)") (class "Default")
      (node (ref "CV1") (pin "P3") (pinfunction "3_P3") (pintype "passive"))
      (node (ref "SHDR_F") (pin "5") (pinfunction "5_5") (pintype "passive"))
    )
    (net (code "22") (name "Net-(CV1_LED-PadA)") (class "Default")
      (node (ref "CV1_LED") (pin "A") (pinfunction "A_A") (pintype "passive"))
      (node (ref "R5") (pin "2") (pinfunction "2_2") (pintype "passive"))
    )
    (net (code "23") (name "Net-(CV2-3)") (class "Default")
      (node (ref "CV2") (pin "P3") (pinfunction "3_P3") (pintype "passive"))
      (node (ref "SHDR_F") (pin "6") (pinfunction "6_6") (pintype "passive"))
    )
    (net (code "24") (name "Net-(CV2_LED-PadA)") (class "Default")
      (node (ref "CV2_LED") (pin "A") (pinfunction "A_A") (pintype "passive"))
      (node (ref "R6") (pin "2") (pinfunction "2_2") (pintype "passive"))
    )
    (net (code "25") (name "Net-(CV3-3)") (class "Default")
      (node (ref "CV3") (pin "P3") (pinfunction "3_P3") (pintype "passive"))
      (node (ref "SHDR_F") (pin "7") (pinfunction "7_7") (pintype "passive"))
    )
    (net (code "26") (name "Net-(CV3_LED-PadA)") (class "Default")
      (node (ref "CV3_LED") (pin "A") (pinfunction "A_A") (pintype "passive"))
      (node (ref "R7") (pin "2") (pinfunction "2_2") (pintype "passive"))
    )
    (net (code "27") (name "Net-(CV4-3)") (class "Default")
      (node (ref "CV4") (pin "P3") (pinfunction "3_P3") (pintype "passive"))
      (node (ref "SHDR_F") (pin "8") (pinfunction "8_8") (pintype "passive"))
    )
    (net (code "28") (name "Net-(CV4_LED-PadA)") (class "Default")
      (node (ref "CV4_LED") (pin "A") (pinfunction "A_A") (pintype "passive"))
      (node (ref "R8") (pin "2") (pinfunction "2_2") (pintype "passive"))
    )
    (net (code "29") (name "Net-(F100-Pad2)") (class "Default")
      (node (ref "F100") (pin "2") (pinfunction "2_2") (pintype "passive"))
      (node (ref "POWER") (pin "1") (pinfunction "-12V_1") (pintype "bidirectional"))
      (node (ref "POWER") (pin "2") (pinfunction "-12V_2") (pintype "bidirectional"))
    )
    (net (code "30") (name "Net-(F101-Pad2)") (class "Default")
      (node (ref "F101") (pin "2") (pinfunction "2_2") (pintype "passive"))
      (node (ref "POWER") (pin "10") (pinfunction "+12V_10") (pintype "bidirectional"))
      (node (ref "POWER") (pin "9") (pinfunction "+12V_9") (pintype "bidirectional"))
    )
    (net (code "31") (name "Net-(IC1A--IN)") (class "Default")
      (node (ref "C4") (pin "1") (pinfunction "1_1") (pintype "passive"))
      (node (ref "IC1") (pin "2") (pinfunction "-IN_2") (pintype "input"))
      (node (ref "R19") (pin "1") (pinfunction "1_1") (pintype "passive"))
      (node (ref "R21") (pin "2") (pinfunction "2_2") (pintype "passive"))
      (node (ref "R9") (pin "2") (pinfunction "2_2") (pintype "passive"))
    )
    (net (code "32") (name "Net-(IC1A-OUT)") (class "Default")
      (node (ref "C4") (pin "2") (pinfunction "2_2") (pintype "passive"))
      (node (ref "IC1") (pin "1") (pinfunction "OUT_1") (pintype "output"))
      (node (ref "R20") (pin "1") (pinfunction "1_1") (pintype "passive"))
    )
    (net (code "33") (name "Net-(IC1B--IN)") (class "Default")
      (node (ref "C3") (pin "1") (pinfunction "1_1") (pintype "passive"))
      (node (ref "IC1") (pin "6") (pinfunction "-IN_6") (pintype "input"))
      (node (ref "R10") (pin "2") (pinfunction "2_2") (pintype "passive"))
      (node (ref "R18") (pin "1") (pinfunction "1_1") (pintype "passive"))
      (node (ref "R22") (pin "2") (pinfunction "2_2") (pintype "passive"))
    )
    (net (code "34") (name "Net-(IC1B-OUT)") (class "Default")
      (node (ref "C3") (pin "2") (pinfunction "2_2") (pintype "passive"))
      (node (ref "IC1") (pin "7") (pinfunction "OUT_7") (pintype "output"))
      (node (ref "R17") (pin "1") (pinfunction "1_1") (pintype "passive"))
    )
    (net (code "35") (name "Net-(IC1C--IN)") (class "Default")
      (node (ref "C102") (pin "1") (pinfunction "1_1") (pintype "passive"))
      (node (ref "IC1") (pin "9") (pinfunction "-IN_9") (pintype "input"))
      (node (ref "R11") (pin "2") (pinfunction "2_2") (pintype "passive"))
      (node (ref "R15") (pin "1") (pinfunction "1_1") (pintype "passive"))
      (node (ref "R23") (pin "2") (pinfunction "2_2") (pintype "passive"))
    )
    (net (code "36") (name "Net-(IC1C-OUT)") (class "Default")
      (node (ref "C102") (pin "2") (pinfunction "2_2") (pintype "passive"))
      (node (ref "IC1") (pin "8") (pinfunction "OUT_8") (pintype "output"))
      (node (ref "R16") (pin "1") (pinfunction "1_1") (pintype "passive"))
    )
    (net (code "37") (name "Net-(IC1D--IN)") (class "Default")
      (node (ref "C2") (pin "1") (pinfunction "1_1") (pintype "passive"))
      (node (ref "IC1") (pin "13") (pinfunction "-IN_13") (pintype "input"))
      (node (ref "R100") (pin "2") (pinfunction "2_2") (pintype "passive"))
      (node (ref "R12") (pin "2") (pinfunction "2_2") (pintype "passive"))
      (node (ref "R13") (pin "1") (pinfunction "1_1") (pintype "passive"))
    )
    (net (code "38") (name "Net-(IC1D-OUT)") (class "Default")
      (node (ref "C2") (pin "2") (pinfunction "2_2") (pintype "passive"))
      (node (ref "IC1") (pin "14") (pinfunction "OUT_14") (pintype "output"))
      (node (ref "R14") (pin "1") (pinfunction "1_1") (pintype "passive"))
    )
    (net (code "39") (name "Net-(IC102A-I)") (class "Default")
      (node (ref "IC102") (pin "2") (pinfunction "I_2") (pintype "input"))
      (node (ref "SHDR_F") (pin "4") (pinfunction "4_4") (pintype "passive"))
    )
    (net (code "40") (name "Net-(IC102A-O)") (class "Default")
      (node (ref "IC102") (pin "4") (pinfunction "O_4") (pintype "tri_state"))
      (node (ref "R102") (pin "1") (pinfunction "1_1") (pintype "passive"))
    )
    (net (code "41") (name "Net-(IC102B-VCC)") (class "Default")
      (node (ref "C112") (pin "1") (pinfunction "1_1") (pintype "passive"))
      (node (ref "C113") (pin "1") (pinfunction "1_1") (pintype "passive"))
      (node (ref "IC102") (pin "5") (pinfunction "VCC_5") (pintype "power_in"))
      (node (ref "IC103") (pin "5") (pinfunction "VCC_5") (pintype "power_in"))
      (node (ref "IC104") (pin "5") (pinfunction "VCC_5") (pintype "power_in"))
      (node (ref "IC105") (pin "5") (pinfunction "VCC_5") (pintype "power_in"))
      (node (ref "SHDR_F") (pin "9") (pinfunction "9_9") (pintype "passive"))
    )
    (net (code "42") (name "Net-(IC103A-I)") (class "Default")
      (node (ref "IC103") (pin "2") (pinfunction "I_2") (pintype "input"))
      (node (ref "SHDR_F") (pin "3") (pinfunction "3_3") (pintype "passive"))
    )
    (net (code "43") (name "Net-(IC103A-O)") (class "Default")
      (node (ref "IC103") (pin "4") (pinfunction "O_4") (pintype "tri_state"))
      (node (ref "R103") (pin "1") (pinfunction "1_1") (pintype "passive"))
    )
    (net (code "44") (name "Net-(IC104A-I)") (class "Default")
      (node (ref "IC104") (pin "2") (pinfunction "I_2") (pintype "input"))
      (node (ref "SHDR_F") (pin "2") (pinfunction "2_2") (pintype "passive"))
    )
    (net (code "45") (name "Net-(IC104A-O)") (class "Default")
      (node (ref "IC104") (pin "4") (pinfunction "O_4") (pintype "tri_state"))
      (node (ref "R104") (pin "1") (pinfunction "1_1") (pintype "passive"))
    )
    (net (code "46") (name "Net-(IC105A-I)") (class "Default")
      (node (ref "IC105") (pin "2") (pinfunction "I_2") (pintype "input"))
      (node (ref "SHDR_F") (pin "1") (pinfunction "1_1") (pintype "passive"))
    )
    (net (code "47") (name "Net-(IC105A-O)") (class "Default")
      (node (ref "IC105") (pin "4") (pinfunction "O_4") (pintype "tri_state"))
      (node (ref "R105") (pin "1") (pinfunction "1_1") (pintype "passive"))
    )
    (net (code "48") (name "Net-(LHDR_F-Pad1)") (class "Default")
      (node (ref "LHDR_F") (pin "1") (pinfunction "1_1") (pintype "passive"))
      (node (ref "R1") (pin "1") (pinfunction "1_1") (pintype "passive"))
    )
    (net (code "49") (name "Net-(LHDR_F-Pad2)") (class "Default")
      (node (ref "LHDR_F") (pin "2") (pinfunction "2_2") (pintype "passive"))
      (node (ref "R2") (pin "1") (pinfunction "1_1") (pintype "passive"))
    )
    (net (code "50") (name "Net-(LHDR_F-Pad3)") (class "Default")
      (node (ref "LHDR_F") (pin "3") (pinfunction "3_3") (pintype "passive"))
      (node (ref "R3") (pin "1") (pinfunction "1_1") (pintype "passive"))
    )
    (net (code "51") (name "Net-(LHDR_F-Pad4)") (class "Default")
      (node (ref "LHDR_F") (pin "4") (pinfunction "4_4") (pintype "passive"))
      (node (ref "R4") (pin "1") (pinfunction "1_1") (pintype "passive"))
    )
    (net (code "52") (name "Net-(LHDR_F-Pad5)") (class "Default")
      (node (ref "LHDR_F") (pin "5") (pinfunction "5_5") (pintype "passive"))
      (node (ref "R5") (pin "1") (pinfunction "1_1") (pintype "passive"))
    )
    (net (code "53") (name "Net-(LHDR_F-Pad6)") (class "Default")
      (node (ref "LHDR_F") (pin "6") (pinfunction "6_6") (pintype "passive"))
      (node (ref "R6") (pin "1") (pinfunction "1_1") (pintype "passive"))
    )
    (net (code "54") (name "Net-(LHDR_F-Pad7)") (class "Default")
      (node (ref "LHDR_F") (pin "7") (pinfunction "7_7") (pintype "passive"))
      (node (ref "R7") (pin "1") (pinfunction "1_1") (pintype "passive"))
    )
    (net (code "55") (name "Net-(LHDR_F-Pad8)") (class "Default")
      (node (ref "LHDR_F") (pin "8") (pinfunction "8_8") (pintype "passive"))
      (node (ref "R8") (pin "1") (pinfunction "1_1") (pintype "passive"))
    )
    (net (code "56") (name "Net-(R1-Pad2)") (class "Default")
      (node (ref "R1") (pin "2") (pinfunction "2_2") (pintype "passive"))
      (node (ref "TRA_LED") (pin "A") (pinfunction "A_A") (pintype "passive"))
    )
    (net (code "57") (name "Net-(R2-Pad2)") (class "Default")
      (node (ref "R2") (pin "2") (pinfunction "2_2") (pintype "passive"))
      (node (ref "TRB_LED") (pin "A") (pinfunction "A_A") (pintype "passive"))
    )
    (net (code "58") (name "Net-(R3-Pad2)") (class "Default")
      (node (ref "R3") (pin "2") (pinfunction "2_2") (pintype "passive"))
      (node (ref "TRC_LED") (pin "A") (pinfunction "A_A") (pintype "passive"))
    )
    (net (code "59") (name "Net-(R4-Pad2)") (class "Default")
      (node (ref "R4") (pin "2") (pinfunction "2_2") (pintype "passive"))
      (node (ref "TRD_LED") (pin "A") (pinfunction "A_A") (pintype "passive"))
    )
    (net (code "60") (name "Net-(T-LEFT-M-Pad1)") (class "Default")
      (node (ref "T-LEFT-M") (pin "1") (pinfunction "1_1") (pintype "passive"))
      (node (ref "U$1") (pin "GND@1") (pinfunction "GND_GND@1") (pintype "bidirectional"))
      (node (ref "U$1") (pin "GND@2") (pinfunction "GND_GND@2") (pintype "bidirectional"))
      (node (ref "U$1") (pin "GND@3") (pinfunction "GND_GND@3") (pintype "bidirectional"))
    )
    (net (code "61") (name "Net-(T-LEFT-M-Pad2)") (class "Default")
      (node (ref "T-LEFT-M") (pin "2") (pinfunction "2_2") (pintype "passive"))
      (node (ref "U$1") (pin "D0") (pinfunction "D0_D0") (pintype "bidirectional"))
    )
    (net (code "62") (name "Net-(T-LEFT-M-Pad3)") (class "Default")
      (node (ref "T-LEFT-M") (pin "3") (pinfunction "3_3") (pintype "passive"))
      (node (ref "U$1") (pin "D1") (pinfunction "D1_D1") (pintype "bidirectional"))
    )
    (net (code "63") (name "Net-(T-LEFT-M-Pad4)") (class "Default")
      (node (ref "T-LEFT-M") (pin "4") (pinfunction "4_4") (pintype "passive"))
      (node (ref "U$1") (pin "D2") (pinfunction "D2_D2") (pintype "bidirectional"))
    )
    (net (code "64") (name "Net-(T-LEFT-M-Pad5)") (class "Default")
      (node (ref "T-LEFT-M") (pin "5") (pinfunction "5_5") (pintype "passive"))
      (node (ref "U$1") (pin "D3") (pinfunction "D3_D3") (pintype "bidirectional"))
    )
    (net (code "65") (name "Net-(T-LEFT-M-Pad6)") (class "Default")
      (node (ref "T-LEFT-M") (pin "6") (pinfunction "6_6") (pintype "passive"))
      (node (ref "U$1") (pin "D4") (pinfunction "D4_D4") (pintype "bidirectional"))
    )
    (net (code "66") (name "Net-(T-LEFT-M-Pad7)") (class "Default")
      (node (ref "T-LEFT-M") (pin "7") (pinfunction "7_7") (pintype "passive"))
      (node (ref "U$1") (pin "D5") (pinfunction "D5_D5") (pintype "bidirectional"))
    )
    (net (code "67") (name "Net-(T-LEFT-M-Pad8)") (class "Default")
      (node (ref "T-LEFT-M") (pin "8") (pinfunction "8_8") (pintype "passive"))
      (node (ref "U$1") (pin "D6") (pinfunction "D6_D6") (pintype "bidirectional"))
    )
    (net (code "68") (name "Net-(T-LEFT-M-Pad9)") (class "Default")
      (node (ref "T-LEFT-M") (pin "9") (pinfunction "9_9") (pintype "passive"))
      (node (ref "U$1") (pin "D7") (pinfunction "D7_D7") (pintype "bidirectional"))
    )
    (net (code "69") (name "Net-(T-LEFT-M-Pad10)") (class "Default")
      (node (ref "T-LEFT-M") (pin "10") (pinfunction "10_10") (pintype "passive"))
      (node (ref "U$1") (pin "D8") (pinfunction "D8_D8") (pintype "bidirectional"))
    )
    (net (code "70") (name "Net-(T-LEFT-M-Pad11)") (class "Default")
      (node (ref "T-LEFT-M") (pin "11") (pinfunction "11_11") (pintype "passive"))
      (node (ref "U$1") (pin "D9") (pinfunction "D9_D9") (pintype "bidirectional"))
    )
    (net (code "71") (name "Net-(T-LEFT-M-Pad12)") (class "Default")
      (node (ref "T-LEFT-M") (pin "12") (pinfunction "12_12") (pintype "passive"))
      (node (ref "U$1") (pin "D10") (pinfunction "D10_D10") (pintype "bidirectional"))
    )
    (net (code "72") (name "Net-(T-LEFT-M-Pad13)") (class "Default")
      (node (ref "T-LEFT-M") (pin "13") (pinfunction "13_13") (pintype "passive"))
      (node (ref "U$1") (pin "D11") (pinfunction "D11_D11") (pintype "bidirectional"))
    )
    (net (code "73") (name "Net-(T-LEFT-M-Pad14)") (class "Default")
      (node (ref "T-LEFT-M") (pin "14") (pinfunction "14_14") (pintype "passive"))
      (node (ref "U$1") (pin "D12") (pinfunction "D12_D12") (pintype "bidirectional"))
    )
    (net (code "74") (name "Net-(T-RIGHT-M-Pad4)") (class "Default")
      (node (ref "T-RIGHT-M") (pin "4") (pinfunction "4_4") (pintype "passive"))
      (node (ref "U$1") (pin "D23/A9") (pinfunction "D23/A9_D23/A9") (pintype "bidirectional"))
    )
    (net (code "75") (name "Net-(T-RIGHT-M-Pad5)") (class "Default")
      (node (ref "T-RIGHT-M") (pin "5") (pinfunction "5_5") (pintype "passive"))
      (node (ref "U$1") (pin "D22/A8") (pinfunction "D22/A8_D22/A8") (pintype "bidirectional"))
    )
    (net (code "76") (name "Net-(T-RIGHT-M-Pad8)") (class "Default")
      (node (ref "T-RIGHT-M") (pin "8") (pinfunction "8_8") (pintype "passive"))
      (node (ref "U$1") (pin "D19/A5") (pinfunction "D19/A5_D19/A5") (pintype "bidirectional"))
    )
    (net (code "77") (name "Net-(T-RIGHT-M-Pad13)") (class "Default")
      (node (ref "T-RIGHT-M") (pin "13") (pinfunction "13_13") (pintype "passive"))
      (node (ref "U$1") (pin "D14/A0") (pinfunction "D14/A0_D14/A0") (pintype "bidirectional"))
    )
    (net (code "78") (name "Net-(T-RIGHT-M-Pad14)") (class "Default")
      (node (ref "T-RIGHT-M") (pin "14") (pinfunction "14_14") (pintype "passive"))
      (node (ref "U$1") (pin "D13/LED") (pinfunction "D13/LED_D13/LED") (pintype "bidirectional"))
    )
    (net (code "79") (name "Net-(TRA-3)") (class "Default")
      (node (ref "R105") (pin "2") (pinfunction "2_2") (pintype "passive"))
      (node (ref "TRA") (pin "P3") (pinfunction "3_P3") (pintype "passive"))
    )
    (net (code "80") (name "Net-(TRB-3)") (class "Default")
      (node (ref "R104") (pin "2") (pinfunction "2_2") (pintype "passive"))
      (node (ref "TRB") (pin "P3") (pinfunction "3_P3") (pintype "passive"))
    )
    (net (code "81") (name "Net-(TRC-3)") (class "Default")
      (node (ref "R103") (pin "2") (pinfunction "2_2") (pintype "passive"))
      (node (ref "TRC") (pin "P3") (pinfunction "3_P3") (pintype "passive"))
    )
    (net (code "82") (name "Net-(TRD-3)") (class "Default")
      (node (ref "R102") (pin "2") (pinfunction "2_2") (pintype "passive"))
      (node (ref "TRD") (pin "P3") (pinfunction "3_P3") (pintype "passive"))
    )
    (net (code "83") (name "Net-(U1-DIN)") (class "Default")
      (node (ref "T-LEFT-F") (pin "13") (pinfunction "13_13") (pintype "passive"))
      (node (ref "U1") (pin "11") (pinfunction "DIN_11") (pintype "input"))
    )
    (net (code "84") (name "Net-(U1-VREFH{slash}VREFOUT)") (class "Default")
      (node (ref "C1") (pin "1") (pinfunction "1_1") (pintype "passive"))
      (node (ref "U1") (pin "3") (pinfunction "VREFH/VREFOUT_3") (pintype "bidirectional"))
    )
    (net (code "85") (name "Net-(U1-~{SYNC})") (class "Default")
      (node (ref "T-LEFT-F") (pin "12") (pinfunction "12_12") (pintype "passive"))
      (node (ref "U1") (pin "9") (pinfunction "~{SYNC}_9") (pintype "input"))
    )
    (net (code "86") (name "SCL") (class "Default")
      (node (ref "II1") (pin "2") (pinfunction "2_2") (pintype "passive"))
      (node (ref "II2") (pin "2") (pinfunction "2_2") (pintype "passive"))
      (node (ref "T-RIGHT-F") (pin "8") (pinfunction "8_8") (pintype "passive"))
    )
    (net (code "87") (name "SCLK") (class "Default")
      (node (ref "T-RIGHT-F") (pin "14") (pinfunction "14_14") (pintype "passive"))
      (node (ref "U1") (pin "10") (pinfunction "SCLK_10") (pintype "input"))
    )
    (net (code "88") (name "SDA") (class "Default")
      (node (ref "II1") (pin "1") (pinfunction "1_1") (pintype "passive"))
      (node (ref "II2") (pin "1") (pinfunction "1_1") (pintype "passive"))
      (node (ref "T-RIGHT-F") (pin "9") (pinfunction "9_9") (pintype "passive"))
    )
    (net (code "89") (name "T-3.3V") (class "Default")
      (node (ref "T-RIGHT-M") (pin "3") (pinfunction "3_3") (pintype "passive"))
      (node (ref "U$1") (pin "3.3V@1") (pinfunction "3.3V_3.3V@1") (pintype "bidirectional"))
      (node (ref "U$1") (pin "3.3V@2") (pinfunction "3.3V_3.3V@2") (pintype "bidirectional"))
      (node (ref "U$1") (pin "3.3V@3") (pinfunction "3.3V_3.3V@3") (pintype "bidirectional"))
    )
    (net (code "90") (name "T-AGND") (class "Default")
      (node (ref "T-RIGHT-M") (pin "2") (pinfunction "2_2") (pintype "passive"))
      (node (ref "U$1") (pin "AGND") (pinfunction "AGND_AGND") (pintype "bidirectional"))
    )
    (net (code "91") (name "T-VIN") (class "Default")
      (node (ref "T-RIGHT-M") (pin "1") (pinfunction "1_1") (pintype "passive"))
      (node (ref "U$1") (pin "VIN") (pinfunction "VIN_VIN") (pintype "bidirectional"))
    )
    (net (code "92") (name "TRA") (class "Default")
      (node (ref "SHDR_M") (pin "1") (pinfunction "1_1") (pintype "passive"))
      (node (ref "T-RIGHT-F") (pin "4") (pinfunction "4_4") (pintype "passive"))
    )
    (net (code "93") (name "TRA-LED") (class "Default")
      (node (ref "LHDR_M") (pin "1") (pinfunction "1_1") (pintype "passive"))
      (node (ref "T-LEFT-F") (pin "2") (pinfunction "2_2") (pintype "passive"))
    )
    (net (code "94") (name "TRB") (class "Default")
      (node (ref "SHDR_M") (pin "2") (pinfunction "2_2") (pintype "passive"))
      (node (ref "T-RIGHT-F") (pin "5") (pinfunction "5_5") (pintype "passive"))
    )
    (net (code "95") (name "TRB-LED") (class "Default")
      (node (ref "LHDR_M") (pin "2") (pinfunction "2_2") (pintype "passive"))
      (node (ref "T-LEFT-F") (pin "3") (pinfunction "3_3") (pintype "passive"))
    )
    (net (code "96") (name "TRC") (class "Default")
      (node (ref "SHDR_M") (pin "3") (pinfunction "3_3") (pintype "passive"))
      (node (ref "T-RIGHT-F") (pin "6") (pinfunction "6_6") (pintype "passive"))
    )
    (net (code "97") (name "TRC-LED") (class "Default")
      (node (ref "LHDR_M") (pin "3") (pinfunction "3_3") (pintype "passive"))
      (node (ref "T-LEFT-F") (pin "4") (pinfunction "4_4") (pintype "passive"))
    )
    (net (code "98") (name "TRD") (class "Default")
      (node (ref "SHDR_M") (pin "4") (pinfunction "4_4") (pintype "passive"))
      (node (ref "T-RIGHT-F") (pin "7") (pinfunction "7_7") (pintype "passive"))
    )
    (net (code "99") (name "TRD-LED") (class "Default")
      (node (ref "LHDR_M") (pin "4") (pinfunction "4_4") (pintype "passive"))
      (node (ref "T-LEFT-F") (pin "9") (pinfunction "9_9") (pintype "passive"))
    )
    (net (code "100") (name "VCC") (class "Default")
      (node (ref "C100") (pin "1") (pinfunction "1_1") (pintype "passive"))
      (node (ref "C107") (pin "1") (pinfunction "1_1") (pintype "passive"))
      (node (ref "C108") (pin "1") (pinfunction "1_1") (pintype "passive"))
      (node (ref "C110") (pin "1") (pinfunction "1_1") (pintype "passive"))
      (node (ref "D100") (pin "2") (pinfunction "C2_2") (pintype "passive"))
      (node (ref "F101") (pin "1") (pinfunction "1_1") (pintype "passive"))
      (node (ref "IC1") (pin "4") (pinfunction "V+_4") (pintype "power_in"))
      (node (ref "IC100") (pin "3") (pinfunction "VI_3") (pintype "input"))
      (node (ref "U100") (pin "2") (pinfunction "VIN_2") (pintype "power_in"))
    )
    (net (code "101") (name "VEE") (class "Default")
      (node (ref "C105") (pin "2") (pinfunction "2_2") (pintype "passive"))
      (node (ref "C106") (pin "2") (pinfunction "2_2") (pintype "passive"))
      (node (ref "C111") (pin "2") (pinfunction "2_2") (pintype "passive"))
      (node (ref "D100") (pin "1") (pinfunction "A1_1") (pintype "passive"))
      (node (ref "F100") (pin "1") (pinfunction "1_1") (pintype "passive"))
      (node (ref "IC1") (pin "11") (pinfunction "V-_11") (pintype "power_in"))
      (node (ref "R101") (pin "1") (pinfunction "1_1") (pintype "passive"))
    )
    (net (code "102") (name "unconnected-(CV1-2-PadP2)") (class "Default")
      (node (ref "CV1") (pin "P2") (pinfunction "2_P2") (pintype "passive"))
    )
    (net (code "103") (name "unconnected-(CV2-2-PadP2)") (class "Default")
      (node (ref "CV2") (pin "P2") (pinfunction "2_P2") (pintype "passive"))
    )
    (net (code "104") (name "unconnected-(CV3-2-PadP2)") (class "Default")
      (node (ref "CV3") (pin "P2") (pinfunction "2_P2") (pintype "passive"))
    )
    (net (code "105") (name "unconnected-(CV4-2-PadP2)") (class "Default")
      (node (ref "CV4") (pin "P2") (pinfunction "2_P2") (pintype "passive"))
    )
    (net (code "106") (name "unconnected-(LHDR_F-Pad9)") (class "Default")
      (node (ref "LHDR_F") (pin "9") (pinfunction "9_9") (pintype "passive"))
    )
    (net (code "107") (name "unconnected-(LHDR_M-Pad9)") (class "Default")
      (node (ref "LHDR_M") (pin "9") (pinfunction "9_9") (pintype "passive"))
    )
    (net (code "108") (name "unconnected-(T-LEFT-F-Pad10)") (class "Default")
      (node (ref "T-LEFT-F") (pin "10") (pinfunction "10_10") (pintype "passive"))
    )
    (net (code "109") (name "unconnected-(T-LEFT-F-Pad11)") (class "Default")
      (node (ref "T-LEFT-F") (pin "11") (pinfunction "11_11") (pintype "passive"))
    )
    (net (code "110") (name "unconnected-(T-LEFT-F-Pad14)") (class "Default")
      (node (ref "T-LEFT-F") (pin "14") (pinfunction "14_14") (pintype "passive"))
    )
    (net (code "111") (name "unconnected-(T-RIGHT-F-Pad13)") (class "Default")
      (node (ref "T-RIGHT-F") (pin "13") (pinfunction "13_13") (pintype "passive"))
    )
    (net (code "112") (name "unconnected-(T-RIGHT-M-Pad6)") (class "Default")
      (node (ref "T-RIGHT-M") (pin "6") (pinfunction "6_6") (pintype "passive"))
    )
    (net (code "113") (name "unconnected-(T-RIGHT-M-Pad7)") (class "Default")
      (node (ref "T-RIGHT-M") (pin "7") (pinfunction "7_7") (pintype "passive"))
    )
    (net (code "114") (name "unconnected-(T-RIGHT-M-Pad9)") (class "Default")
      (node (ref "T-RIGHT-M") (pin "9") (pinfunction "9_9") (pintype "passive"))
    )
    (net (code "115") (name "unconnected-(T-RIGHT-M-Pad10)") (class "Default")
      (node (ref "T-RIGHT-M") (pin "10") (pinfunction "10_10") (pintype "passive"))
    )
    (net (code "116") (name "unconnected-(T-RIGHT-M-Pad11)") (class "Default")
      (node (ref "T-RIGHT-M") (pin "11") (pinfunction "11_11") (pintype "passive"))
    )
    (net (code "117") (name "unconnected-(T-RIGHT-M-Pad12)") (class "Default")
      (node (ref "T-RIGHT-M") (pin "12") (pinfunction "12_12") (pintype "passive"))
    )
    (net (code "118") (name "unconnected-(TRA-2-PadP2)") (class "Default")
      (node (ref "TRA") (pin "P2") (pinfunction "2_P2") (pintype "passive"))
    )
    (net (code "119") (name "unconnected-(TRB-2-PadP2)") (class "Default")
      (node (ref "TRB") (pin "P2") (pinfunction "2_P2") (pintype "passive"))
    )
    (net (code "120") (name "unconnected-(TRC-2-PadP2)") (class "Default")
      (node (ref "TRC") (pin "P2") (pinfunction "2_P2") (pintype "passive"))
    )
    (net (code "121") (name "unconnected-(TRD-2-PadP2)") (class "Default")
      (node (ref "TRD") (pin "P2") (pinfunction "2_P2") (pintype "passive"))
    )
    (net (code "122") (name "unconnected-(U$1-PadA10)") (class "Default")
      (node (ref "U$1") (pin "A10") (pinfunction "A10_A10") (pintype "bidirectional"))
    )
    (net (code "123") (name "unconnected-(U$1-PadA11)") (class "Default")
      (node (ref "U$1") (pin "A11") (pinfunction "A11_A11") (pintype "bidirectional"))
    )
    (net (code "124") (name "unconnected-(U$1-PadA12)") (class "Default")
      (node (ref "U$1") (pin "A12") (pinfunction "A12_A12") (pintype "bidirectional"))
    )
    (net (code "125") (name "unconnected-(U$1-PadA13)") (class "Default")
      (node (ref "U$1") (pin "A13") (pinfunction "A13_A13") (pintype "bidirectional"))
    )
    (net (code "126") (name "unconnected-(U$1-PadA14{slash}DAC)") (class "Default")
      (node (ref "U$1") (pin "A14/DAC") (pinfunction "A14/DAC_A14/DAC") (pintype "bidirectional"))
    )
    (net (code "127") (name "unconnected-(U$1-PadAREF)") (class "Default")
      (node (ref "U$1") (pin "AREF") (pinfunction "AREF_AREF") (pintype "bidirectional"))
    )
    (net (code "128") (name "unconnected-(U$1-PadD15{slash}A1)") (class "Default")
      (node (ref "U$1") (pin "D15/A1") (pinfunction "D15/A1_D15/A1") (pintype "bidirectional"))
    )
    (net (code "129") (name "unconnected-(U$1-PadD16{slash}A2)") (class "Default")
      (node (ref "U$1") (pin "D16/A2") (pinfunction "D16/A2_D16/A2") (pintype "bidirectional"))
    )
    (net (code "130") (name "unconnected-(U$1-PadD17{slash}A3)") (class "Default")
      (node (ref "U$1") (pin "D17/A3") (pinfunction "D17/A3_D17/A3") (pintype "bidirectional"))
    )
    (net (code "131") (name "unconnected-(U$1-PadD18{slash}A4)") (class "Default")
      (node (ref "U$1") (pin "D18/A4") (pinfunction "D18/A4_D18/A4") (pintype "bidirectional"))
    )
    (net (code "132") (name "unconnected-(U$1-PadD20{slash}A6)") (class "Default")
      (node (ref "U$1") (pin "D20/A6") (pinfunction "D20/A6_D20/A6") (pintype "bidirectional"))
    )
    (net (code "133") (name "unconnected-(U$1-PadD21{slash}A7)") (class "Default")
      (node (ref "U$1") (pin "D21/A7") (pinfunction "D21/A7_D21/A7") (pintype "bidirectional"))
    )
    (net (code "134") (name "unconnected-(U$1-PadD24)") (class "Default")
      (node (ref "U$1") (pin "D24") (pinfunction "D24_D24") (pintype "bidirectional"))
    )
    (net (code "135") (name "unconnected-(U$1-PadD25)") (class "Default")
      (node (ref "U$1") (pin "D25") (pinfunction "D25_D25") (pintype "bidirectional"))
    )
    (net (code "136") (name "unconnected-(U$1-PadD26{slash}A15)") (class "Default")
      (node (ref "U$1") (pin "D26/A15") (pinfunction "D26/A15_D26/A15") (pintype "bidirectional"))
    )
    (net (code "137") (name "unconnected-(U$1-PadD27{slash}A16)") (class "Default")
      (node (ref "U$1") (pin "D27/A16") (pinfunction "D27/A16_D27/A16") (pintype "bidirectional"))
    )
    (net (code "138") (name "unconnected-(U$1-PadD28{slash}A17)") (class "Default")
      (node (ref "U$1") (pin "D28/A17") (pinfunction "D28/A17_D28/A17") (pintype "bidirectional"))
    )
    (net (code "139") (name "unconnected-(U$1-PadD29{slash}A18)") (class "Default")
      (node (ref "U$1") (pin "D29/A18") (pinfunction "D29/A18_D29/A18") (pintype "bidirectional"))
    )
    (net (code "140") (name "unconnected-(U$1-PadD30{slash}A19)") (class "Default")
      (node (ref "U$1") (pin "D30/A19") (pinfunction "D30/A19_D30/A19") (pintype "bidirectional"))
    )
    (net (code "141") (name "unconnected-(U$1-PadD31{slash}A20)") (class "Default")
      (node (ref "U$1") (pin "D31/A20") (pinfunction "D31/A20_D31/A20") (pintype "bidirectional"))
    )
    (net (code "142") (name "unconnected-(U$1-PadD32)") (class "Default")
      (node (ref "U$1") (pin "D32") (pinfunction "D32_D32") (pintype "bidirectional"))
    )
    (net (code "143") (name "unconnected-(U$1-PadD33)") (class "Default")
      (node (ref "U$1") (pin "D33") (pinfunction "D33_D33") (pintype "bidirectional"))
    )
    (net (code "144") (name "unconnected-(U$1-PadPROGRAM)") (class "Default")
      (node (ref "U$1") (pin "PROGRAM") (pinfunction "PROGRAM_PROGRAM") (pintype "bidirectional"))
    )
    (net (code "145") (name "unconnected-(U$1-PadRESET)") (class "Default")
      (node (ref "U$1") (pin "RESET") (pinfunction "RESET_RESET") (pintype "bidirectional"))
    )
    (net (code "146") (name "unconnected-(U$1-PadVBAT)") (class "Default")
      (node (ref "U$1") (pin "VBAT") (pinfunction "VBAT_VBAT") (pintype "bidirectional"))
    )
    (net (code "147") (name "unconnected-(U100-NC-Pad8)") (class "Default")
      (node (ref "U100") (pin "8") (pinfunction "NC_8") (pintype "no_connect"))
    )
    (net (code "148") (name "unconnected-(U100-NC_2-Pad7)") (class "Default")
      (node (ref "U100") (pin "7") (pinfunction "NC_2_7") (pintype "no_connect"))
    )
    (net (code "149") (name "unconnected-(U100-NC_3-Pad1)") (class "Default")
      (node (ref "U100") (pin "1") (pinfunction "NC_3_1") (pintype "no_connect"))
    )
    (net (code "150") (name "unconnected-(U100-TEMP-Pad3)") (class "Default")
      (node (ref "U100") (pin "3") (pinfunction "TEMP_3") (pintype "input"))
    )
    (net (code "151") (name "unconnected-(U100-TRIM-Pad5)") (class "Default")
      (node (ref "U100") (pin "5") (pinfunction "TRIM_5") (pintype "passive"))
    )
  )
)
